# FridgeFanExtender.net
KiCad netlist of a schematic drawn in EAGLE
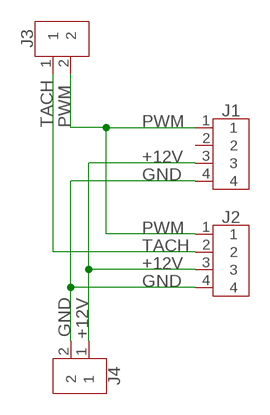
[diagram p0: schematic, sheet 1]

(export (version "E")
  (design (tool "Eeschema 10.0.6"))
  (components
    (comp (ref "J1")
      (value "B4B-XH-A")
      (footprint "eagle-import:B4B-XH-A")
      (fields (field (name "MANUFACTURER") "JST Sales America Inc.") (field (name "MPN") "B4B-XH-A(LF)(SN)"))
      (libsource (lib "eagle-import") (part "B4B-XH-A"))
    )
    (comp (ref "J2")
      (value "B4B-XH-A")
      (footprint "eagle-import:B4B-XH-A")
      (fields (field (name "MANUFACTURER") "JST Sales America Inc.") (field (name "MPN") "B4B-XH-A(LF)(SN)"))
      (libsource (lib "eagle-import") (part "B4B-XH-A"))
    )
    (comp (ref "J3")
      (value "B2B-XH-A")
      (footprint "eagle-import:B2B-XH-A")
      (fields
        (field (name "MANUFACTURER") "JST Sales America Inc. ")
        (field (name "MPN") "B2B-XH-A(LF)(SN) ")
      )
      (libsource (lib "eagle-import") (part "B2B-XH-A"))
    )
    (comp (ref "J4")
      (value "B2B-XH-A")
      (footprint "eagle-import:B2B-XH-A")
      (fields
        (field (name "MANUFACTURER") "JST Sales America Inc. ")
        (field (name "MPN") "B2B-XH-A(LF)(SN) ")
      )
      (libsource (lib "eagle-import") (part "B2B-XH-A"))
    )
  )
  (nets
    (net (code "1") (name "/+12V") (class "Default")
      (node (ref "J1") (pin "3") (pinfunction "3_3") (pintype "bidirectional"))
      (node (ref "J2") (pin "3") (pinfunction "3_3") (pintype "bidirectional"))
      (node (ref "J4") (pin "1") (pinfunction "1_1") (pintype "bidirectional"))
    )
    (net (code "2") (name "/GND") (class "Default")
      (node (ref "J1") (pin "4") (pinfunction "4_4") (pintype "bidirectional"))
      (node (ref "J2") (pin "4") (pinfunction "4_4") (pintype "bidirectional"))
      (node (ref "J4") (pin "2") (pinfunction "2_2") (pintype "bidirectional"))
    )
    (net (code "3") (name "/PWM") (class "Default")
      (node (ref "J1") (pin "1") (pinfunction "1_1") (pintype "bidirectional"))
      (node (ref "J2") (pin "1") (pinfunction "1_1") (pintype "bidirectional"))
      (node (ref "J3") (pin "2") (pinfunction "2_2") (pintype "bidirectional"))
    )
    (net (code "4") (name "/TACH") (class "Default")
      (node (ref "J2") (pin "2") (pinfunction "2_2") (pintype "bidirectional"))
      (node (ref "J3") (pin "1") (pinfunction "1_1") (pintype "bidirectional"))
    )
    (net (code "5") (name "unconnected-(J1-Pad2)") (class "Default")
      (node (ref "J1") (pin "2") (pinfunction "2_2") (pintype "bidirectional"))
    )
  )
)
